# RadioAdapterBoardV4.net
KiCad netlist of a schematic drawn in EAGLE
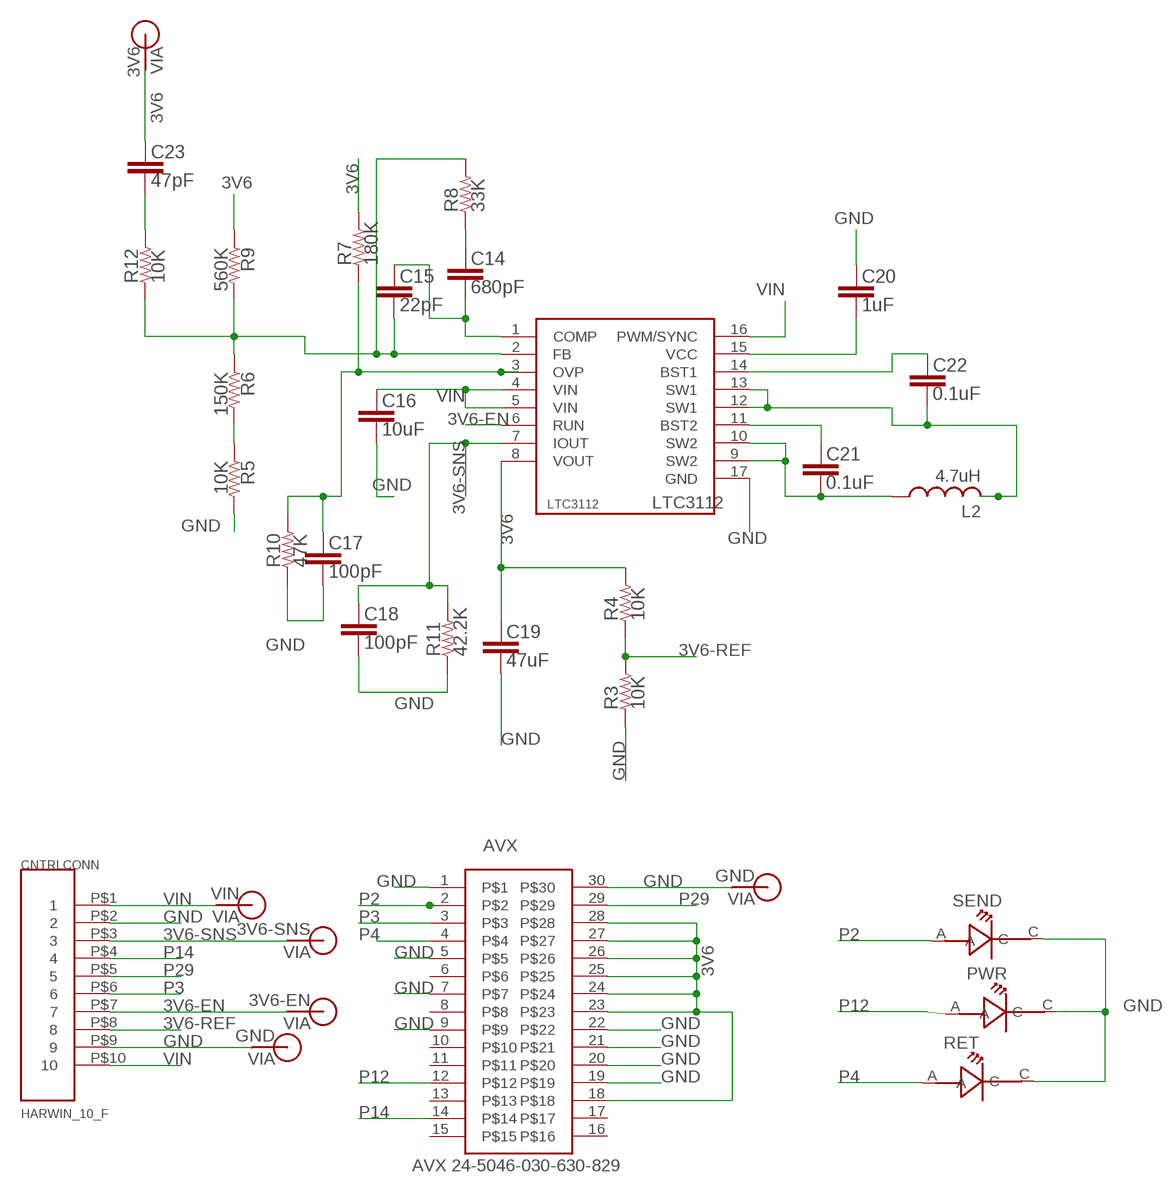
[diagram p0: schematic, sheet 1]

(export (version "E")
  (design (tool "Eeschema 10.0.6"))
  (components
    (comp (ref "AVX")
      (value "AVX-24-5046-030-630-829")
      (footprint "eagle-import:AVX-24-5046-630-829")
      (libsource (lib "eagle-import") (part "AVX-24-5046-030-630-829"))
    )
    (comp (ref "C14")
      (value "680pF")
      (footprint "eagle-import:0805")
      (libsource (lib "eagle-import") (part "CAP0805"))
    )
    (comp (ref "C15")
      (value "22pF")
      (footprint "eagle-import:0805")
      (libsource (lib "eagle-import") (part "CAP0805"))
    )
    (comp (ref "C16")
      (value "10uF")
      (footprint "eagle-import:0805")
      (libsource (lib "eagle-import") (part "CAP0805"))
    )
    (comp (ref "C17")
      (value "100pF")
      (footprint "eagle-import:0805")
      (libsource (lib "eagle-import") (part "CAP0805"))
    )
    (comp (ref "C18")
      (value "100pF")
      (footprint "eagle-import:0805")
      (libsource (lib "eagle-import") (part "CAP0805"))
    )
    (comp (ref "C19")
      (value "47uF")
      (footprint "eagle-import:0805")
      (libsource (lib "eagle-import") (part "CAP0805"))
    )
    (comp (ref "C20")
      (value "1uF")
      (footprint "eagle-import:0805")
      (libsource (lib "eagle-import") (part "CAP0805"))
    )
    (comp (ref "C21")
      (value "0.1uF")
      (footprint "eagle-import:0805")
      (libsource (lib "eagle-import") (part "CAP0805"))
    )
    (comp (ref "C22")
      (value "0.1uF")
      (footprint "eagle-import:0805")
      (libsource (lib "eagle-import") (part "CAP0805"))
    )
    (comp (ref "C23")
      (value "47pF")
      (footprint "eagle-import:0805")
      (libsource (lib "eagle-import") (part "CAP0805"))
    )
    (comp (ref "CNTRLCONN")
      (value "HARWIN_10_F")
      (footprint "eagle-import:HARWIN_DATAMATE_10_F")
      (libsource (lib "eagle-import") (part "HARWIN_10_F"))
    )
    (comp (ref "L2")
      (value "4.7uH")
      (footprint "eagle-import:L3225M")
      (libsource (lib "eagle-import") (part "L-USL3225M"))
    )
    (comp (ref "LTC3112")
      (value "LTC3112")
      (footprint "eagle-import:DHD16")
      (libsource (lib "eagle-import") (part "LTC3112"))
    )
    (comp (ref "PWR")
      (value "LT-T673-Q1R2-25-Z")
      (footprint "eagle-import:PLCC-2")
      (libsource (lib "eagle-import") (part "LT-T673-Q1R2-25-Z"))
    )
    (comp (ref "R3")
      (value "10K")
      (footprint "eagle-import:0805")
      (libsource (lib "eagle-import") (part "RES0805"))
    )
    (comp (ref "R4")
      (value "10K")
      (footprint "eagle-import:0805")
      (libsource (lib "eagle-import") (part "RES0805"))
    )
    (comp (ref "R5")
      (value "10K")
      (footprint "eagle-import:0805")
      (libsource (lib "eagle-import") (part "RES0805"))
    )
    (comp (ref "R6")
      (value "150K")
      (footprint "eagle-import:0805")
      (libsource (lib "eagle-import") (part "RES0805"))
    )
    (comp (ref "R7")
      (value "180K")
      (footprint "eagle-import:0805")
      (libsource (lib "eagle-import") (part "RES0805"))
    )
    (comp (ref "R8")
      (value "33K")
      (footprint "eagle-import:0805")
      (libsource (lib "eagle-import") (part "RES0805"))
    )
    (comp (ref "R9")
      (value "560K")
      (footprint "eagle-import:0805")
      (libsource (lib "eagle-import") (part "RES0805"))
    )
    (comp (ref "R10")
      (value "47K")
      (footprint "eagle-import:0805")
      (libsource (lib "eagle-import") (part "RES0805"))
    )
    (comp (ref "R11")
      (value "42.2K")
      (footprint "eagle-import:0805")
      (libsource (lib "eagle-import") (part "RES0805"))
    )
    (comp (ref "R12")
      (value "10K")
      (footprint "eagle-import:0805")
      (libsource (lib "eagle-import") (part "RES0805"))
    )
    (comp (ref "RET")
      (value "LT-T673-Q1R2-25-Z")
      (footprint "eagle-import:PLCC-2")
      (libsource (lib "eagle-import") (part "LT-T673-Q1R2-25-Z"))
    )
    (comp (ref "SEND")
      (value "LT-T673-Q1R2-25-Z")
      (footprint "eagle-import:PLCC-2")
      (libsource (lib "eagle-import") (part "LT-T673-Q1R2-25-Z"))
    )
    (comp (ref "V1")
      (value "VIN")
      (footprint "eagle-import:VIA-60MIL-SQ")
      (libsource (lib "eagle-import") (part "VIA60MIL-SQ"))
    )
    (comp (ref "V2")
      (value "3V6-SNS")
      (footprint "eagle-import:VIA-60MIL-SQ")
      (libsource (lib "eagle-import") (part "VIA60MIL-SQ"))
    )
    (comp (ref "V3")
      (value "GND")
      (footprint "eagle-import:VIA-60MIL-SQ")
      (libsource (lib "eagle-import") (part "VIA60MIL-SQ"))
    )
    (comp (ref "V4")
      (value "GND")
      (footprint "eagle-import:VIA-60MIL-SQ")
      (libsource (lib "eagle-import") (part "VIA60MIL-SQ"))
    )
    (comp (ref "V5")
      (value "3V6")
      (footprint "eagle-import:VIA-60MIL-SQ")
      (libsource (lib "eagle-import") (part "VIA60MIL-SQ"))
    )
    (comp (ref "V6")
      (value "3V6-EN")
      (footprint "eagle-import:VIA-60MIL-SQ")
      (libsource (lib "eagle-import") (part "VIA60MIL-SQ"))
    )
  )
  (nets
    (net (code "1") (name "/3V6") (class "Default")
      (node (ref "AVX") (pin "18") (pinfunction "P$18_18") (pintype "bidirectional"))
      (node (ref "AVX") (pin "23") (pinfunction "P$23_23") (pintype "bidirectional"))
      (node (ref "AVX") (pin "24") (pinfunction "P$24_24") (pintype "bidirectional"))
      (node (ref "AVX") (pin "25") (pinfunction "P$25_25") (pintype "bidirectional"))
      (node (ref "AVX") (pin "26") (pinfunction "P$26_26") (pintype "bidirectional"))
      (node (ref "AVX") (pin "27") (pinfunction "P$27_27") (pintype "bidirectional"))
      (node (ref "AVX") (pin "28") (pinfunction "P$28_28") (pintype "bidirectional"))
      (node (ref "C19") (pin "1") (pinfunction "P$1_1") (pintype "passive"))
      (node (ref "C23") (pin "1") (pinfunction "P$1_1") (pintype "passive"))
      (node (ref "LTC3112") (pin "8") (pinfunction "VOUT_8") (pintype "bidirectional"))
      (node (ref "R4") (pin "2") (pinfunction "2_2") (pintype "passive"))
      (node (ref "R7") (pin "2") (pinfunction "2_2") (pintype "passive"))
      (node (ref "R9") (pin "1") (pinfunction "1_1") (pintype "passive"))
      (node (ref "V5") (pin "P$1") (pinfunction "P$1_P$1") (pintype "bidirectional"))
    )
    (net (code "2") (name "/3V6-EN") (class "Default")
      (node (ref "CNTRLCONN") (pin "P$7") (pinfunction "7_P$7") (pintype "bidirectional"))
      (node (ref "LTC3112") (pin "6") (pinfunction "RUN_6") (pintype "bidirectional"))
      (node (ref "V6") (pin "P$1") (pinfunction "P$1_P$1") (pintype "bidirectional"))
    )
    (net (code "3") (name "/3V6-REF") (class "Default")
      (node (ref "CNTRLCONN") (pin "P$8") (pinfunction "8_P$8") (pintype "bidirectional"))
      (node (ref "R3") (pin "2") (pinfunction "2_2") (pintype "passive"))
      (node (ref "R4") (pin "1") (pinfunction "1_1") (pintype "passive"))
    )
    (net (code "4") (name "/3V6-SNS") (class "Default")
      (node (ref "C18") (pin "1") (pinfunction "P$1_1") (pintype "passive"))
      (node (ref "CNTRLCONN") (pin "P$3") (pinfunction "3_P$3") (pintype "bidirectional"))
      (node (ref "LTC3112") (pin "7") (pinfunction "IOUT_7") (pintype "bidirectional"))
      (node (ref "R11") (pin "2") (pinfunction "2_2") (pintype "passive"))
      (node (ref "V2") (pin "P$1") (pinfunction "P$1_P$1") (pintype "bidirectional"))
    )
    (net (code "5") (name "/GND") (class "Default")
      (node (ref "AVX") (pin "1") (pinfunction "P$1_1") (pintype "bidirectional"))
      (node (ref "AVX") (pin "19") (pinfunction "P$19_19") (pintype "bidirectional"))
      (node (ref "AVX") (pin "20") (pinfunction "P$20_20") (pintype "bidirectional"))
      (node (ref "AVX") (pin "21") (pinfunction "P$21_21") (pintype "bidirectional"))
      (node (ref "AVX") (pin "22") (pinfunction "P$22_22") (pintype "bidirectional"))
      (node (ref "AVX") (pin "30") (pinfunction "P$30_30") (pintype "bidirectional"))
      (node (ref "AVX") (pin "5") (pinfunction "P$5_5") (pintype "bidirectional"))
      (node (ref "AVX") (pin "7") (pinfunction "P$7_7") (pintype "bidirectional"))
      (node (ref "AVX") (pin "9") (pinfunction "P$9_9") (pintype "bidirectional"))
      (node (ref "C16") (pin "2") (pinfunction "P$2_2") (pintype "passive"))
      (node (ref "C17") (pin "2") (pinfunction "P$2_2") (pintype "passive"))
      (node (ref "C18") (pin "2") (pinfunction "P$2_2") (pintype "passive"))
      (node (ref "C19") (pin "2") (pinfunction "P$2_2") (pintype "passive"))
      (node (ref "C20") (pin "1") (pinfunction "P$1_1") (pintype "passive"))
      (node (ref "CNTRLCONN") (pin "P$2") (pinfunction "2_P$2") (pintype "bidirectional"))
      (node (ref "CNTRLCONN") (pin "P$9") (pinfunction "9_P$9") (pintype "bidirectional"))
      (node (ref "LTC3112") (pin "17") (pinfunction "GND_17") (pintype "bidirectional"))
      (node (ref "PWR") (pin "C") (pinfunction "C_C") (pintype "bidirectional"))
      (node (ref "R10") (pin "1") (pinfunction "1_1") (pintype "passive"))
      (node (ref "R11") (pin "1") (pinfunction "1_1") (pintype "passive"))
      (node (ref "R3") (pin "1") (pinfunction "1_1") (pintype "passive"))
      (node (ref "R5") (pin "2") (pinfunction "2_2") (pintype "passive"))
      (node (ref "RET") (pin "C") (pinfunction "C_C") (pintype "bidirectional"))
      (node (ref "SEND") (pin "C") (pinfunction "C_C") (pintype "bidirectional"))
      (node (ref "V3") (pin "P$1") (pinfunction "P$1_P$1") (pintype "bidirectional"))
      (node (ref "V4") (pin "P$1") (pinfunction "P$1_P$1") (pintype "bidirectional"))
    )
    (net (code "6") (name "/P2") (class "Default")
      (node (ref "AVX") (pin "2") (pinfunction "P$2_2") (pintype "bidirectional"))
      (node (ref "SEND") (pin "A") (pinfunction "A_A") (pintype "bidirectional"))
    )
    (net (code "7") (name "/P3") (class "Default")
      (node (ref "AVX") (pin "3") (pinfunction "P$3_3") (pintype "bidirectional"))
      (node (ref "CNTRLCONN") (pin "P$6") (pinfunction "6_P$6") (pintype "bidirectional"))
    )
    (net (code "8") (name "/P4") (class "Default")
      (node (ref "AVX") (pin "4") (pinfunction "P$4_4") (pintype "bidirectional"))
      (node (ref "RET") (pin "A") (pinfunction "A_A") (pintype "bidirectional"))
    )
    (net (code "9") (name "/P12") (class "Default")
      (node (ref "AVX") (pin "12") (pinfunction "P$12_12") (pintype "bidirectional"))
      (node (ref "PWR") (pin "A") (pinfunction "A_A") (pintype "bidirectional"))
    )
    (net (code "10") (name "/P14") (class "Default")
      (node (ref "AVX") (pin "14") (pinfunction "P$14_14") (pintype "bidirectional"))
      (node (ref "CNTRLCONN") (pin "P$4") (pinfunction "4_P$4") (pintype "bidirectional"))
    )
    (net (code "11") (name "/P29") (class "Default")
      (node (ref "AVX") (pin "29") (pinfunction "P$29_29") (pintype "bidirectional"))
      (node (ref "CNTRLCONN") (pin "P$5") (pinfunction "5_P$5") (pintype "bidirectional"))
    )
    (net (code "12") (name "/VIN") (class "Default")
      (node (ref "C16") (pin "1") (pinfunction "P$1_1") (pintype "passive"))
      (node (ref "CNTRLCONN") (pin "P$1") (pinfunction "1_P$1") (pintype "bidirectional"))
      (node (ref "CNTRLCONN") (pin "P$10") (pinfunction "10_P$10") (pintype "bidirectional"))
      (node (ref "LTC3112") (pin "16") (pinfunction "PWM/SYNC_16") (pintype "bidirectional"))
      (node (ref "LTC3112") (pin "4") (pinfunction "VIN_4") (pintype "bidirectional"))
      (node (ref "LTC3112") (pin "5") (pinfunction "VIN_5") (pintype "bidirectional"))
      (node (ref "V1") (pin "P$1") (pinfunction "P$1_P$1") (pintype "bidirectional"))
    )
    (net (code "13") (name "Net-(C14-P$1)") (class "Default")
      (node (ref "C14") (pin "1") (pinfunction "P$1_1") (pintype "passive"))
      (node (ref "R8") (pin "1") (pinfunction "1_1") (pintype "passive"))
    )
    (net (code "14") (name "Net-(C14-P$2)") (class "Default")
      (node (ref "C14") (pin "2") (pinfunction "P$2_2") (pintype "passive"))
      (node (ref "C15") (pin "1") (pinfunction "P$1_1") (pintype "passive"))
      (node (ref "LTC3112") (pin "1") (pinfunction "COMP_1") (pintype "bidirectional"))
    )
    (net (code "15") (name "Net-(C15-P$2)") (class "Default")
      (node (ref "C15") (pin "2") (pinfunction "P$2_2") (pintype "passive"))
      (node (ref "LTC3112") (pin "2") (pinfunction "FB_2") (pintype "bidirectional"))
      (node (ref "R12") (pin "1") (pinfunction "1_1") (pintype "passive"))
      (node (ref "R6") (pin "1") (pinfunction "1_1") (pintype "passive"))
      (node (ref "R8") (pin "2") (pinfunction "2_2") (pintype "passive"))
      (node (ref "R9") (pin "2") (pinfunction "2_2") (pintype "passive"))
    )
    (net (code "16") (name "Net-(C17-P$1)") (class "Default")
      (node (ref "C17") (pin "1") (pinfunction "P$1_1") (pintype "passive"))
      (node (ref "LTC3112") (pin "3") (pinfunction "OVP_3") (pintype "bidirectional"))
      (node (ref "R10") (pin "2") (pinfunction "2_2") (pintype "passive"))
      (node (ref "R7") (pin "1") (pinfunction "1_1") (pintype "passive"))
    )
    (net (code "17") (name "Net-(C20-P$2)") (class "Default")
      (node (ref "C20") (pin "2") (pinfunction "P$2_2") (pintype "passive"))
      (node (ref "LTC3112") (pin "15") (pinfunction "VCC_15") (pintype "bidirectional"))
    )
    (net (code "18") (name "Net-(C21-P$1)") (class "Default")
      (node (ref "C21") (pin "1") (pinfunction "P$1_1") (pintype "passive"))
      (node (ref "LTC3112") (pin "11") (pinfunction "BST2_11") (pintype "bidirectional"))
    )
    (net (code "19") (name "Net-(C21-P$2)") (class "Default")
      (node (ref "C21") (pin "2") (pinfunction "P$2_2") (pintype "passive"))
      (node (ref "L2") (pin "1") (pinfunction "1_1") (pintype "passive"))
      (node (ref "LTC3112") (pin "10") (pinfunction "SW2_10") (pintype "bidirectional"))
      (node (ref "LTC3112") (pin "9") (pinfunction "SW2_9") (pintype "bidirectional"))
    )
    (net (code "20") (name "Net-(C22-P$1)") (class "Default")
      (node (ref "C22") (pin "1") (pinfunction "P$1_1") (pintype "passive"))
      (node (ref "LTC3112") (pin "14") (pinfunction "BST1_14") (pintype "bidirectional"))
    )
    (net (code "21") (name "Net-(C22-P$2)") (class "Default")
      (node (ref "C22") (pin "2") (pinfunction "P$2_2") (pintype "passive"))
      (node (ref "L2") (pin "2") (pinfunction "2_2") (pintype "passive"))
      (node (ref "LTC3112") (pin "12") (pinfunction "SW1_12") (pintype "bidirectional"))
      (node (ref "LTC3112") (pin "13") (pinfunction "SW1_13") (pintype "bidirectional"))
    )
    (net (code "22") (name "Net-(C23-P$2)") (class "Default")
      (node (ref "C23") (pin "2") (pinfunction "P$2_2") (pintype "passive"))
      (node (ref "R12") (pin "2") (pinfunction "2_2") (pintype "passive"))
    )
    (net (code "23") (name "Net-(R5-Pad1)") (class "Default")
      (node (ref "R5") (pin "1") (pinfunction "1_1") (pintype "passive"))
      (node (ref "R6") (pin "2") (pinfunction "2_2") (pintype "passive"))
    )
    (net (code "24") (name "unconnected-(AVX-P$6-Pad6)") (class "Default")
      (node (ref "AVX") (pin "6") (pinfunction "P$6_6") (pintype "bidirectional"))
    )
    (net (code "25") (name "unconnected-(AVX-P$8-Pad8)") (class "Default")
      (node (ref "AVX") (pin "8") (pinfunction "P$8_8") (pintype "bidirectional"))
    )
    (net (code "26") (name "unconnected-(AVX-P$10-Pad10)") (class "Default")
      (node (ref "AVX") (pin "10") (pinfunction "P$10_10") (pintype "bidirectional"))
    )
    (net (code "27") (name "unconnected-(AVX-P$11-Pad11)") (class "Default")
      (node (ref "AVX") (pin "11") (pinfunction "P$11_11") (pintype "bidirectional"))
    )
    (net (code "28") (name "unconnected-(AVX-P$13-Pad13)") (class "Default")
      (node (ref "AVX") (pin "13") (pinfunction "P$13_13") (pintype "bidirectional"))
    )
    (net (code "29") (name "unconnected-(AVX-P$15-Pad15)") (class "Default")
      (node (ref "AVX") (pin "15") (pinfunction "P$15_15") (pintype "bidirectional"))
    )
    (net (code "30") (name "unconnected-(AVX-P$16-Pad16)") (class "Default")
      (node (ref "AVX") (pin "16") (pinfunction "P$16_16") (pintype "bidirectional"))
    )
    (net (code "31") (name "unconnected-(AVX-P$17-Pad17)") (class "Default")
      (node (ref "AVX") (pin "17") (pinfunction "P$17_17") (pintype "bidirectional"))
    )
  )
)
